# PS2_KB_to_serial_adaptor.net
KiCad netlist of a schematic drawn in EAGLE
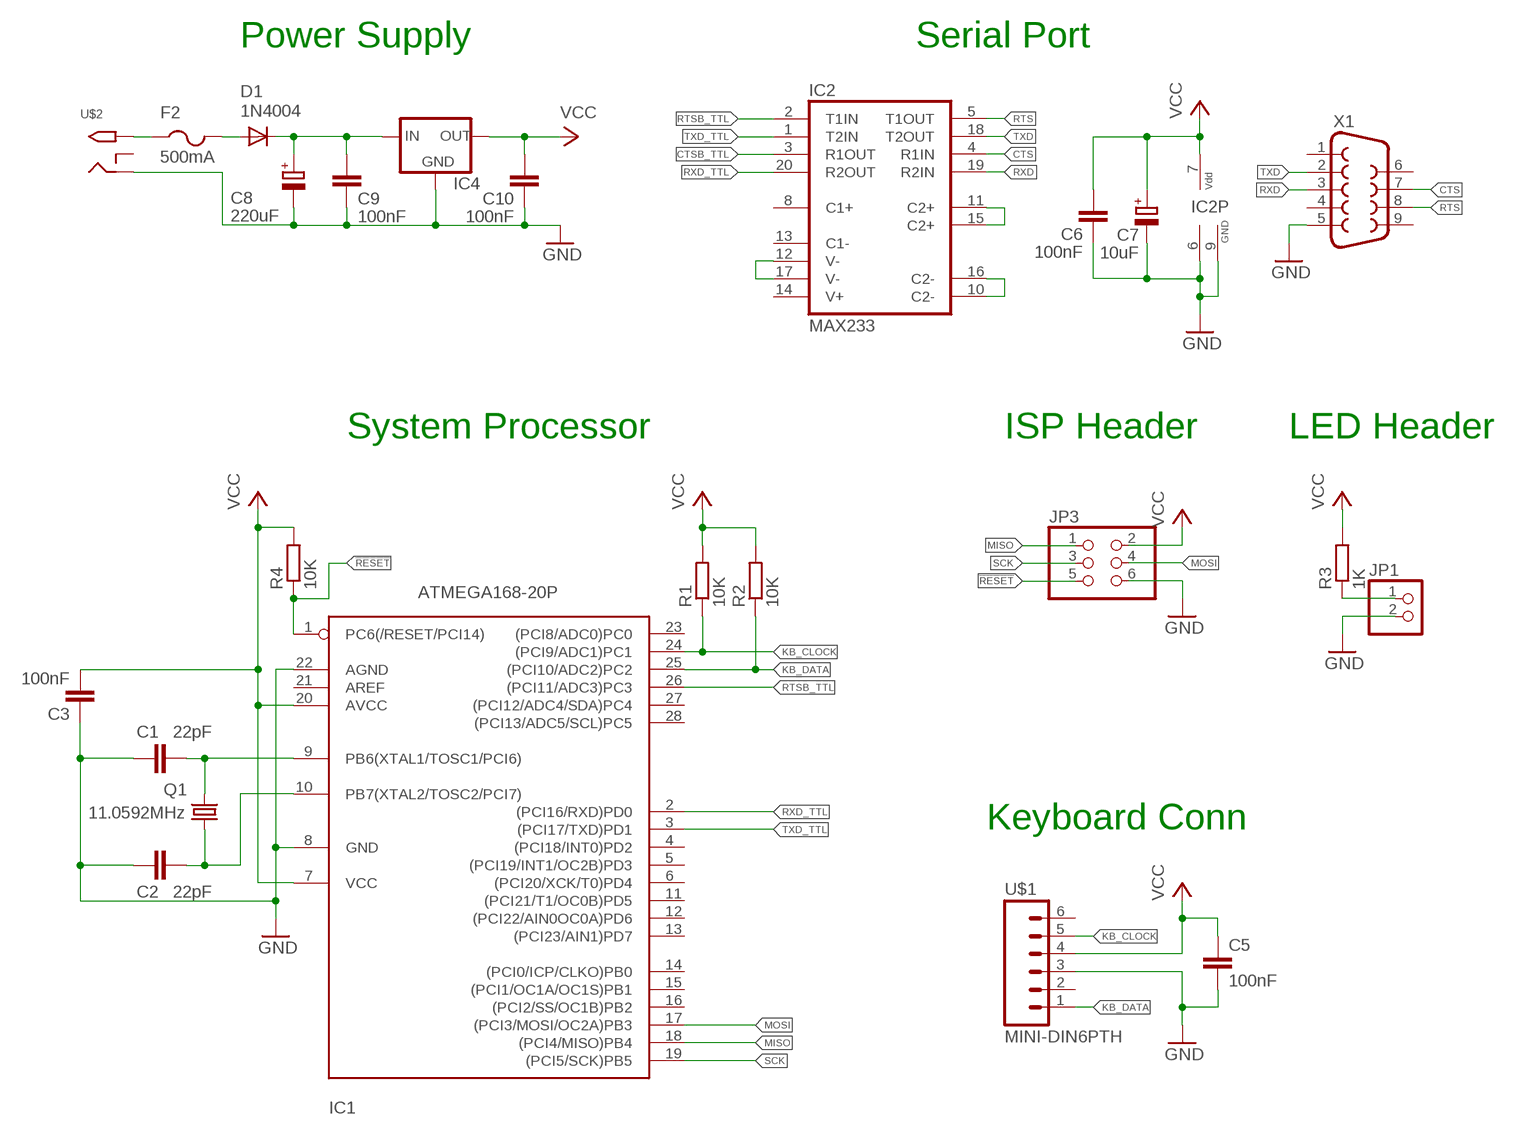
[diagram p0: schematic, sheet 1]

(export (version "E")
  (design (tool "Eeschema 10.0.6"))
  (components
    (comp (ref "C1")
      (value "22pF")
      (footprint "eagle-import:C025-024X044")
      (libsource (lib "eagle-import") (part "C-EU025-024X044"))
    )
    (comp (ref "C2")
      (value "22pF")
      (footprint "eagle-import:C025-024X044")
      (libsource (lib "eagle-import") (part "C-EU025-024X044"))
    )
    (comp (ref "C3")
      (value "100nF")
      (footprint "eagle-import:C025-024X044")
      (libsource (lib "eagle-import") (part "C-EU025-024X044"))
    )
    (comp (ref "C5")
      (value "100nF")
      (footprint "eagle-import:C050-024X044")
      (libsource (lib "eagle-import") (part "C-EU050-024X044"))
    )
    (comp (ref "C6")
      (value "100nF")
      (footprint "eagle-import:C025-024X044")
      (libsource (lib "eagle-import") (part "C-EU025-024X044"))
    )
    (comp (ref "C7")
      (value "10uF")
      (footprint "eagle-import:E2,5-5")
      (libsource (lib "eagle-import") (part "CPOL-EUE2.5-5"))
    )
    (comp (ref "C8")
      (value "220uF")
      (footprint "eagle-import:E2,5-7")
      (libsource (lib "eagle-import") (part "CPOL-EUE2.5-7"))
    )
    (comp (ref "C9")
      (value "100nF")
      (footprint "eagle-import:C025-024X044")
      (libsource (lib "eagle-import") (part "C-EU025-024X044"))
    )
    (comp (ref "C10")
      (value "100nF")
      (footprint "eagle-import:C025-024X044")
      (libsource (lib "eagle-import") (part "C-EU025-024X044"))
    )
    (comp (ref "D1")
      (value "1N4004")
      (footprint "eagle-import:DO41-10")
      (libsource (lib "eagle-import") (part "1N4004"))
    )
    (comp (ref "F2")
      (value "500mA")
      (footprint "eagle-import:1812")
      (libsource (lib "eagle-import") (part "PTCFUSE-1812"))
    )
    (comp (ref "IC1")
      (value "ATMEGA168-20P")
      (footprint "eagle-import:DIL28-3")
      (libsource (lib "eagle-import") (part "ATMEGA168P-20"))
    )
    (comp (ref "IC2")
      (value "MAX233")
      (footprint "eagle-import:DIL20")
      (libsource (lib "eagle-import") (part "MAX233"))
    )
    (comp (ref "IC4")
      (value "78XXL")
      (footprint "eagle-import:78XXL")
      (libsource (lib "eagle-import") (part "78XXL"))
    )
    (comp (ref "JP1")
      (value "PINHD-1X2")
      (footprint "eagle-import:1X02")
      (libsource (lib "eagle-import") (part "PINHD-1X2"))
    )
    (comp (ref "JP3")
      (value "PINHD-2X3")
      (footprint "eagle-import:2X03")
      (libsource (lib "eagle-import") (part "PINHD-2X3"))
    )
    (comp (ref "Q1")
      (value "11.0592MHz")
      (footprint "eagle-import:HC49U-V")
      (libsource (lib "eagle-import") (part "CRYSTALHC49U-V"))
    )
    (comp (ref "R1")
      (value "10K")
      (footprint "eagle-import:0207_2V")
      (libsource (lib "eagle-import") (part "R-EU_0207/2V"))
    )
    (comp (ref "R2")
      (value "10K")
      (footprint "eagle-import:0207_2V")
      (libsource (lib "eagle-import") (part "R-EU_0207/2V"))
    )
    (comp (ref "R3")
      (value "1K")
      (footprint "eagle-import:0207_2V")
      (libsource (lib "eagle-import") (part "R-EU_0207/2V"))
    )
    (comp (ref "R4")
      (value "10K")
      (footprint "eagle-import:0207_7")
      (libsource (lib "eagle-import") (part "R-EU_0207/7"))
    )
    (comp (ref "U$1")
      (value "MINI-DIN6PTH")
      (footprint "eagle-import:MINI-DIN6")
      (libsource (lib "eagle-import") (part "MINI-DIN6PTH"))
    )
    (comp (ref "U$2")
      (value "2.1MMJACKTHM")
      (footprint "eagle-import:PJ-102A")
      (libsource (lib "eagle-import") (part "2.1MMJACKTHM"))
    )
    (comp (ref "X1")
      (value "F09HP")
      (footprint "eagle-import:F09HP")
      (libsource (lib "eagle-import") (part "F09HP"))
    )
  )
  (nets
    (net (code "1") (name "/~{RESET}") (class "Default")
      (node (ref "IC1") (pin "1") (pinfunction "PC6(/RESET/PCI14)_1") (pintype "bidirectional"))
      (node (ref "JP3") (pin "5") (pinfunction "5_5") (pintype "passive"))
      (node (ref "R4") (pin "1") (pinfunction "1_1") (pintype "passive"))
    )
    (net (code "2") (name "CTS") (class "Default")
      (node (ref "IC2") (pin "4") (pinfunction "R1IN_4") (pintype "input"))
      (node (ref "X1") (pin "7") (pinfunction "7_7") (pintype "passive"))
    )
    (net (code "3") (name "CTSB_TTL") (class "Default")
      (node (ref "IC2") (pin "3") (pinfunction "R1OUT_3") (pintype "output"))
    )
    (net (code "4") (name "GND") (class "Default")
      (node (ref "C1") (pin "1") (pinfunction "1_1") (pintype "passive"))
      (node (ref "C10") (pin "1") (pinfunction "1_1") (pintype "passive"))
      (node (ref "C2") (pin "1") (pinfunction "1_1") (pintype "passive"))
      (node (ref "C3") (pin "1") (pinfunction "1_1") (pintype "passive"))
      (node (ref "C5") (pin "1") (pinfunction "1_1") (pintype "passive"))
      (node (ref "C6") (pin "1") (pinfunction "1_1") (pintype "passive"))
      (node (ref "C7") (pin "-") (pinfunction "-_-") (pintype "passive"))
      (node (ref "C8") (pin "-") (pinfunction "-_-") (pintype "passive"))
      (node (ref "C9") (pin "1") (pinfunction "1_1") (pintype "passive"))
      (node (ref "IC1") (pin "22") (pinfunction "AGND_22") (pintype "bidirectional"))
      (node (ref "IC1") (pin "8") (pinfunction "GND_8") (pintype "bidirectional"))
      (node (ref "IC2") (pin "6") (pinfunction "GND_6") (pintype "power_in"))
      (node (ref "IC2") (pin "9") (pinfunction "GND_9") (pintype "power_in"))
      (node (ref "IC4") (pin "GND") (pinfunction "GND_GND") (pintype "input"))
      (node (ref "JP1") (pin "2") (pinfunction "2_2") (pintype "passive"))
      (node (ref "JP3") (pin "6") (pinfunction "6_6") (pintype "passive"))
      (node (ref "U$1") (pin "3") (pinfunction "3_3") (pintype "passive"))
      (node (ref "U$2") (pin "RING") (pinfunction "RING_RING") (pintype "bidirectional"))
      (node (ref "X1") (pin "5") (pinfunction "5_5") (pintype "passive"))
    )
    (net (code "5") (name "KB_CLOCK") (class "Default")
      (node (ref "IC1") (pin "24") (pinfunction "(PCI9/ADC1)PC1_24") (pintype "bidirectional"))
      (node (ref "R1") (pin "1") (pinfunction "1_1") (pintype "passive"))
      (node (ref "U$1") (pin "5") (pinfunction "5_5") (pintype "passive"))
    )
    (net (code "6") (name "KB_DATA") (class "Default")
      (node (ref "IC1") (pin "25") (pinfunction "(PCI10/ADC2)PC2_25") (pintype "bidirectional"))
      (node (ref "R2") (pin "1") (pinfunction "1_1") (pintype "passive"))
      (node (ref "U$1") (pin "1") (pinfunction "1_1") (pintype "passive"))
    )
    (net (code "7") (name "MISO") (class "Default")
      (node (ref "IC1") (pin "18") (pinfunction "(PCI4/MISO)PB4_18") (pintype "bidirectional"))
      (node (ref "JP3") (pin "1") (pinfunction "1_1") (pintype "passive"))
    )
    (net (code "8") (name "MOSI") (class "Default")
      (node (ref "IC1") (pin "17") (pinfunction "(PCI3/MOSI/OC2A)PB3_17") (pintype "bidirectional"))
      (node (ref "JP3") (pin "4") (pinfunction "4_4") (pintype "passive"))
    )
    (net (code "9") (name "Net-(C8-Pad+)") (class "Default")
      (node (ref "C8") (pin "+") (pinfunction "+_+") (pintype "passive"))
      (node (ref "C9") (pin "2") (pinfunction "2_2") (pintype "passive"))
      (node (ref "D1") (pin "C") (pinfunction "C_C") (pintype "passive"))
      (node (ref "IC4") (pin "IN") (pinfunction "IN_IN") (pintype "input"))
    )
    (net (code "10") (name "Net-(D1-PadA)") (class "Default")
      (node (ref "D1") (pin "A") (pinfunction "A_A") (pintype "passive"))
      (node (ref "F2") (pin "2") (pinfunction "2_2") (pintype "passive"))
    )
    (net (code "11") (name "Net-(F2-Pad1)") (class "Default")
      (node (ref "F2") (pin "1") (pinfunction "1_1") (pintype "passive"))
      (node (ref "U$2") (pin "TIP") (pinfunction "TIP_TIP") (pintype "bidirectional"))
    )
    (net (code "12") (name "Net-(IC1-PB6(XTAL1{slash}TOSC1{slash}PCI6))") (class "Default")
      (node (ref "C1") (pin "2") (pinfunction "2_2") (pintype "passive"))
      (node (ref "IC1") (pin "9") (pinfunction "PB6(XTAL1/TOSC1/PCI6)_9") (pintype "bidirectional"))
      (node (ref "Q1") (pin "2") (pinfunction "2_2") (pintype "passive"))
    )
    (net (code "13") (name "Net-(IC1-PB7(XTAL2{slash}TOSC2{slash}PCI7))") (class "Default")
      (node (ref "C2") (pin "2") (pinfunction "2_2") (pintype "passive"))
      (node (ref "IC1") (pin "10") (pinfunction "PB7(XTAL2/TOSC2/PCI7)_10") (pintype "bidirectional"))
      (node (ref "Q1") (pin "1") (pinfunction "1_1") (pintype "passive"))
    )
    (net (code "14") (name "Net-(IC2A-C2+-Pad11)") (class "Default")
      (node (ref "IC2") (pin "11") (pinfunction "C2+_11") (pintype "bidirectional"))
      (node (ref "IC2") (pin "15") (pinfunction "C2+_15") (pintype "bidirectional"))
    )
    (net (code "15") (name "Net-(IC2A-C2--Pad10)") (class "Default")
      (node (ref "IC2") (pin "10") (pinfunction "C2-_10") (pintype "bidirectional"))
      (node (ref "IC2") (pin "16") (pinfunction "C2-_16") (pintype "bidirectional"))
    )
    (net (code "16") (name "Net-(IC2A-V--Pad12)") (class "Default")
      (node (ref "IC2") (pin "12") (pinfunction "V-_12") (pintype "bidirectional"))
      (node (ref "IC2") (pin "17") (pinfunction "V-_17") (pintype "bidirectional"))
    )
    (net (code "17") (name "Net-(JP1-Pad1)") (class "Default")
      (node (ref "JP1") (pin "1") (pinfunction "1_1") (pintype "passive"))
      (node (ref "R3") (pin "1") (pinfunction "1_1") (pintype "passive"))
    )
    (net (code "18") (name "RTS") (class "Default")
      (node (ref "IC2") (pin "5") (pinfunction "T1OUT_5") (pintype "output"))
      (node (ref "X1") (pin "8") (pinfunction "8_8") (pintype "passive"))
    )
    (net (code "19") (name "RTSB_TTL") (class "Default")
      (node (ref "IC1") (pin "26") (pinfunction "(PCI11/ADC3)PC3_26") (pintype "bidirectional"))
      (node (ref "IC2") (pin "2") (pinfunction "T1IN_2") (pintype "input"))
    )
    (net (code "20") (name "RXD") (class "Default")
      (node (ref "IC2") (pin "19") (pinfunction "R2IN_19") (pintype "input"))
      (node (ref "X1") (pin "3") (pinfunction "3_3") (pintype "passive"))
    )
    (net (code "21") (name "RXD_TTL") (class "Default")
      (node (ref "IC1") (pin "2") (pinfunction "(PCI16/RXD)PD0_2") (pintype "bidirectional"))
      (node (ref "IC2") (pin "20") (pinfunction "R2OUT_20") (pintype "output"))
    )
    (net (code "22") (name "SCK") (class "Default")
      (node (ref "IC1") (pin "19") (pinfunction "(PCI5/SCK)PB5_19") (pintype "bidirectional"))
      (node (ref "JP3") (pin "3") (pinfunction "3_3") (pintype "passive"))
    )
    (net (code "23") (name "TXD") (class "Default")
      (node (ref "IC2") (pin "18") (pinfunction "T2OUT_18") (pintype "output"))
      (node (ref "X1") (pin "2") (pinfunction "2_2") (pintype "passive"))
    )
    (net (code "24") (name "TXD_TTL") (class "Default")
      (node (ref "IC1") (pin "3") (pinfunction "(PCI17/TXD)PD1_3") (pintype "bidirectional"))
      (node (ref "IC2") (pin "1") (pinfunction "T2IN_1") (pintype "input"))
    )
    (net (code "25") (name "VCC") (class "Default")
      (node (ref "C10") (pin "2") (pinfunction "2_2") (pintype "passive"))
      (node (ref "C3") (pin "2") (pinfunction "2_2") (pintype "passive"))
      (node (ref "C5") (pin "2") (pinfunction "2_2") (pintype "passive"))
      (node (ref "C6") (pin "2") (pinfunction "2_2") (pintype "passive"))
      (node (ref "C7") (pin "+") (pinfunction "+_+") (pintype "passive"))
      (node (ref "IC1") (pin "20") (pinfunction "AVCC_20") (pintype "bidirectional"))
      (node (ref "IC1") (pin "7") (pinfunction "VCC_7") (pintype "bidirectional"))
      (node (ref "IC2") (pin "7") (pinfunction "VDD_7") (pintype "power_in"))
      (node (ref "IC4") (pin "OUT") (pinfunction "OUT_OUT") (pintype "passive"))
      (node (ref "JP3") (pin "2") (pinfunction "2_2") (pintype "passive"))
      (node (ref "R1") (pin "2") (pinfunction "2_2") (pintype "passive"))
      (node (ref "R2") (pin "2") (pinfunction "2_2") (pintype "passive"))
      (node (ref "R3") (pin "2") (pinfunction "2_2") (pintype "passive"))
      (node (ref "R4") (pin "2") (pinfunction "2_2") (pintype "passive"))
      (node (ref "U$1") (pin "4") (pinfunction "4_4") (pintype "passive"))
    )
    (net (code "26") (name "unconnected-(IC1-(PCI0{slash}ICP{slash}CLKO)PB0-Pad14)") (class "Default")
      (node (ref "IC1") (pin "14") (pinfunction "(PCI0/ICP/CLKO)PB0_14") (pintype "bidirectional"))
    )
    (net (code "27") (name "unconnected-(IC1-(PCI1{slash}OC1A{slash}OC1S)PB1-Pad15)") (class "Default")
      (node (ref "IC1") (pin "15") (pinfunction "(PCI1/OC1A/OC1S)PB1_15") (pintype "bidirectional"))
    )
    (net (code "28") (name "unconnected-(IC1-(PCI2{slash}SS{slash}OC1B)PB2-Pad16)") (class "Default")
      (node (ref "IC1") (pin "16") (pinfunction "(PCI2/SS/OC1B)PB2_16") (pintype "bidirectional"))
    )
    (net (code "29") (name "unconnected-(IC1-(PCI8{slash}ADC0)PC0-Pad23)") (class "Default")
      (node (ref "IC1") (pin "23") (pinfunction "(PCI8/ADC0)PC0_23") (pintype "bidirectional"))
    )
    (net (code "30") (name "unconnected-(IC1-(PCI12{slash}ADC4{slash}SDA)PC4-Pad27)") (class "Default")
      (node (ref "IC1") (pin "27") (pinfunction "(PCI12/ADC4/SDA)PC4_27") (pintype "bidirectional"))
    )
    (net (code "31") (name "unconnected-(IC1-(PCI13{slash}ADC5{slash}SCL)PC5-Pad28)") (class "Default")
      (node (ref "IC1") (pin "28") (pinfunction "(PCI13/ADC5/SCL)PC5_28") (pintype "bidirectional"))
    )
    (net (code "32") (name "unconnected-(IC1-(PCI18{slash}INT0)PD2-Pad4)") (class "Default")
      (node (ref "IC1") (pin "4") (pinfunction "(PCI18/INT0)PD2_4") (pintype "bidirectional"))
    )
    (net (code "33") (name "unconnected-(IC1-(PCI19{slash}INT1{slash}OC2B)PD3-Pad5)") (class "Default")
      (node (ref "IC1") (pin "5") (pinfunction "(PCI19/INT1/OC2B)PD3_5") (pintype "bidirectional"))
    )
    (net (code "34") (name "unconnected-(IC1-(PCI20{slash}XCK{slash}T0)PD4-Pad6)") (class "Default")
      (node (ref "IC1") (pin "6") (pinfunction "(PCI20/XCK/T0)PD4_6") (pintype "bidirectional"))
    )
    (net (code "35") (name "unconnected-(IC1-(PCI21{slash}T1{slash}OC0B)PD5-Pad11)") (class "Default")
      (node (ref "IC1") (pin "11") (pinfunction "(PCI21/T1/OC0B)PD5_11") (pintype "bidirectional"))
    )
    (net (code "36") (name "unconnected-(IC1-(PCI22{slash}AIN0OC0A)PD6-Pad12)") (class "Default")
      (node (ref "IC1") (pin "12") (pinfunction "(PCI22/AIN0OC0A)PD6_12") (pintype "bidirectional"))
    )
    (net (code "37") (name "unconnected-(IC1-(PCI23{slash}AIN1)PD7-Pad13)") (class "Default")
      (node (ref "IC1") (pin "13") (pinfunction "(PCI23/AIN1)PD7_13") (pintype "bidirectional"))
    )
    (net (code "38") (name "unconnected-(IC1-AREF-Pad21)") (class "Default")
      (node (ref "IC1") (pin "21") (pinfunction "AREF_21") (pintype "bidirectional"))
    )
    (net (code "39") (name "unconnected-(IC2A-C1+-Pad8)") (class "Default")
      (node (ref "IC2") (pin "8") (pinfunction "C1+_8") (pintype "bidirectional"))
    )
    (net (code "40") (name "unconnected-(IC2A-C1--Pad13)") (class "Default")
      (node (ref "IC2") (pin "13") (pinfunction "C1-_13") (pintype "bidirectional"))
    )
    (net (code "41") (name "unconnected-(IC2A-V+-Pad14)") (class "Default")
      (node (ref "IC2") (pin "14") (pinfunction "V+_14") (pintype "bidirectional"))
    )
    (net (code "42") (name "unconnected-(U$1-Pad2)") (class "Default")
      (node (ref "U$1") (pin "2") (pinfunction "2_2") (pintype "passive"))
    )
    (net (code "43") (name "unconnected-(U$1-Pad6)") (class "Default")
      (node (ref "U$1") (pin "6") (pinfunction "6_6") (pintype "passive"))
    )
    (net (code "44") (name "unconnected-(U$2-PadRING_SW)") (class "Default")
      (node (ref "U$2") (pin "RING_SW") (pinfunction "RING_SW_RING_SW") (pintype "bidirectional"))
    )
    (net (code "45") (name "unconnected-(X1-Pad1)") (class "Default")
      (node (ref "X1") (pin "1") (pinfunction "1_1") (pintype "passive"))
    )
    (net (code "46") (name "unconnected-(X1-Pad4)") (class "Default")
      (node (ref "X1") (pin "4") (pinfunction "4_4") (pintype "passive"))
    )
    (net (code "47") (name "unconnected-(X1-Pad6)") (class "Default")
      (node (ref "X1") (pin "6") (pinfunction "6_6") (pintype "passive"))
    )
    (net (code "48") (name "unconnected-(X1-Pad9)") (class "Default")
      (node (ref "X1") (pin "9") (pinfunction "9_9") (pintype "passive"))
    )
  )
)
